# 2_FPGA.net
KiCad netlist of a schematic drawn in Altium Designer
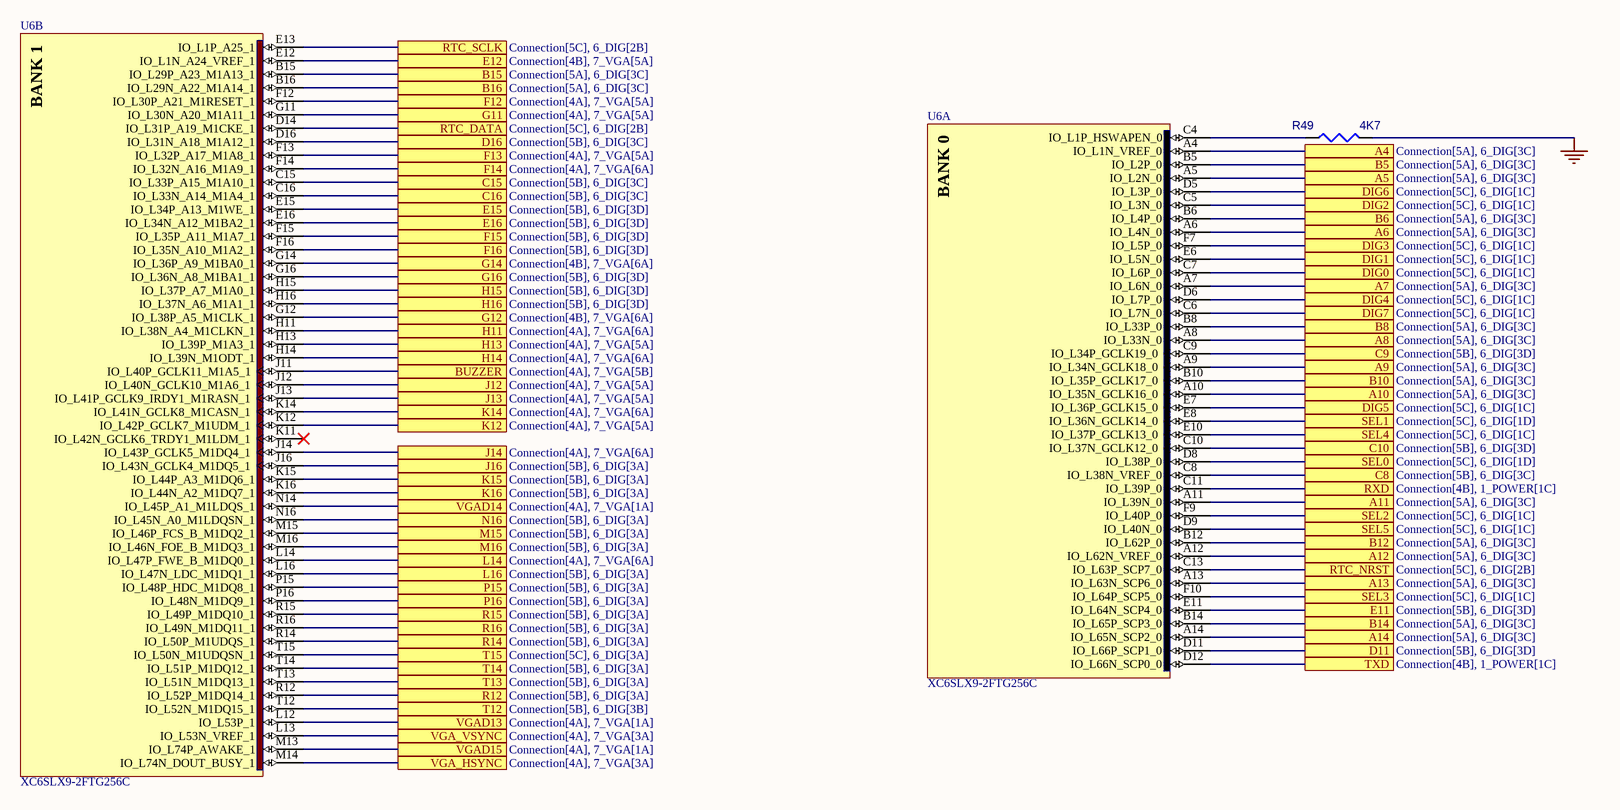
[diagram p0: 2_FPGA.SchDoc]

(export (version "E")
  (design (tool "Eeschema 10.0.6"))
  (components
    (comp (ref "R49") (value "4K7") (footprint "0603") (libsource (lib "*") (part "R")))
    (comp (ref "U6")
      (value "XC6SLX9-2FTG256C")
      (footprint "FTG256")
      (libsource (lib "Xilinx Spartan-6") (part "XC6SLX9-2FTG256C"))
    )
  )
  (nets
    (net (code "1") (name "/A4") (class "Default")
      (node (ref "U6") (pin "A4") (pinfunction "IO_L1N_VREF_0_A4") (pintype "bidirectional"))
    )
    (net (code "2") (name "/A5") (class "Default")
      (node (ref "U6") (pin "A5") (pinfunction "IO_L2N_0_A5") (pintype "bidirectional"))
    )
    (net (code "3") (name "/A6") (class "Default")
      (node (ref "U6") (pin "A6") (pinfunction "IO_L4N_0_A6") (pintype "bidirectional"))
    )
    (net (code "4") (name "/A7") (class "Default")
      (node (ref "U6") (pin "A7") (pinfunction "IO_L6N_0_A7") (pintype "bidirectional"))
    )
    (net (code "5") (name "/A8") (class "Default")
      (node (ref "U6") (pin "A8") (pinfunction "IO_L33N_0_A8") (pintype "bidirectional"))
    )
    (net (code "6") (name "/A9") (class "Default")
      (node (ref "U6") (pin "A9") (pinfunction "IO_L34N_GCLK18_0_A9") (pintype "bidirectional"))
    )
    (net (code "7") (name "/A10") (class "Default")
      (node (ref "U6") (pin "A10") (pinfunction "IO_L35N_GCLK16_0_A10") (pintype "bidirectional"))
    )
    (net (code "8") (name "/A11") (class "Default")
      (node (ref "U6") (pin "A11") (pinfunction "IO_L39N_0_A11") (pintype "bidirectional"))
    )
    (net (code "9") (name "/A12") (class "Default")
      (node (ref "U6") (pin "A12") (pinfunction "IO_L62N_VREF_0_A12") (pintype "bidirectional"))
    )
    (net (code "10") (name "/A13") (class "Default")
      (node (ref "U6") (pin "A13") (pinfunction "IO_L63N_SCP6_0_A13") (pintype "bidirectional"))
    )
    (net (code "11") (name "/A14") (class "Default")
      (node (ref "U6") (pin "A14") (pinfunction "IO_L65N_SCP2_0_A14") (pintype "bidirectional"))
    )
    (net (code "12") (name "/B5") (class "Default")
      (node (ref "U6") (pin "B5") (pinfunction "IO_L2P_0_B5") (pintype "bidirectional"))
    )
    (net (code "13") (name "/B6") (class "Default")
      (node (ref "U6") (pin "B6") (pinfunction "IO_L4P_0_B6") (pintype "bidirectional"))
    )
    (net (code "14") (name "/B8") (class "Default")
      (node (ref "U6") (pin "B8") (pinfunction "IO_L33P_0_B8") (pintype "bidirectional"))
    )
    (net (code "15") (name "/B10") (class "Default")
      (node (ref "U6") (pin "B10") (pinfunction "IO_L35P_GCLK17_0_B10") (pintype "bidirectional"))
    )
    (net (code "16") (name "/B12") (class "Default")
      (node (ref "U6") (pin "B12") (pinfunction "IO_L62P_0_B12") (pintype "bidirectional"))
    )
    (net (code "17") (name "/B14") (class "Default")
      (node (ref "U6") (pin "B14") (pinfunction "IO_L65P_SCP3_0_B14") (pintype "bidirectional"))
    )
    (net (code "18") (name "/B15") (class "Default")
      (node (ref "U6") (pin "B15") (pinfunction "IO_L29P_A23_M1A13_1_B15") (pintype "bidirectional"))
    )
    (net (code "19") (name "/B16") (class "Default")
      (node (ref "U6") (pin "B16") (pinfunction "IO_L29N_A22_M1A14_1_B16") (pintype "bidirectional"))
    )
    (net (code "20") (name "/BUZZER") (class "Default")
      (node (ref "U6") (pin "J11") (pinfunction "IO_L40P_GCLK11_M1A5_1_J11") (pintype "bidirectional"))
    )
    (net (code "21") (name "/C8") (class "Default")
      (node (ref "U6") (pin "C8") (pinfunction "IO_L38N_VREF_0_C8") (pintype "bidirectional"))
    )
    (net (code "22") (name "/C9") (class "Default")
      (node (ref "U6") (pin "C9") (pinfunction "IO_L34P_GCLK19_0_C9") (pintype "bidirectional"))
    )
    (net (code "23") (name "/C10") (class "Default")
      (node (ref "U6") (pin "C10") (pinfunction "IO_L37N_GCLK12_0_C10") (pintype "bidirectional"))
    )
    (net (code "24") (name "/C15") (class "Default")
      (node (ref "U6") (pin "C15") (pinfunction "IO_L33P_A15_M1A10_1_C15") (pintype "bidirectional"))
    )
    (net (code "25") (name "/C16") (class "Default")
      (node (ref "U6") (pin "C16") (pinfunction "IO_L33N_A14_M1A4_1_C16") (pintype "bidirectional"))
    )
    (net (code "26") (name "/D11") (class "Default")
      (node (ref "U6") (pin "D11") (pinfunction "IO_L66P_SCP1_0_D11") (pintype "bidirectional"))
    )
    (net (code "27") (name "/D16") (class "Default")
      (node (ref "U6") (pin "D16") (pinfunction "IO_L31N_A18_M1A12_1_D16") (pintype "bidirectional"))
    )
    (net (code "28") (name "/DIG0") (class "Default")
      (node (ref "U6") (pin "C7") (pinfunction "IO_L6P_0_C7") (pintype "bidirectional"))
    )
    (net (code "29") (name "/DIG1") (class "Default")
      (node (ref "U6") (pin "E6") (pinfunction "IO_L5N_0_E6") (pintype "bidirectional"))
    )
    (net (code "30") (name "/DIG2") (class "Default")
      (node (ref "U6") (pin "C5") (pinfunction "IO_L3N_0_C5") (pintype "bidirectional"))
    )
    (net (code "31") (name "/DIG3") (class "Default")
      (node (ref "U6") (pin "F7") (pinfunction "IO_L5P_0_F7") (pintype "bidirectional"))
    )
    (net (code "32") (name "/DIG4") (class "Default")
      (node (ref "U6") (pin "D6") (pinfunction "IO_L7P_0_D6") (pintype "bidirectional"))
    )
    (net (code "33") (name "/DIG5") (class "Default")
      (node (ref "U6") (pin "E7") (pinfunction "IO_L36P_GCLK15_0_E7") (pintype "bidirectional"))
    )
    (net (code "34") (name "/DIG6") (class "Default")
      (node (ref "U6") (pin "D5") (pinfunction "IO_L3P_0_D5") (pintype "bidirectional"))
    )
    (net (code "35") (name "/DIG7") (class "Default")
      (node (ref "U6") (pin "C6") (pinfunction "IO_L7N_0_C6") (pintype "bidirectional"))
    )
    (net (code "36") (name "/E11") (class "Default")
      (node (ref "U6") (pin "E11") (pinfunction "IO_L64N_SCP4_0_E11") (pintype "bidirectional"))
    )
    (net (code "37") (name "/E12") (class "Default")
      (node (ref "U6") (pin "E12") (pinfunction "IO_L1N_A24_VREF_1_E12") (pintype "bidirectional"))
    )
    (net (code "38") (name "/E15") (class "Default")
      (node (ref "U6") (pin "E15") (pinfunction "IO_L34P_A13_M1WE_1_E15") (pintype "bidirectional"))
    )
    (net (code "39") (name "/E16") (class "Default")
      (node (ref "U6") (pin "E16") (pinfunction "IO_L34N_A12_M1BA2_1_E16") (pintype "bidirectional"))
    )
    (net (code "40") (name "/F12") (class "Default")
      (node (ref "U6") (pin "F12") (pinfunction "IO_L30P_A21_M1RESET_1_F12") (pintype "bidirectional"))
    )
    (net (code "41") (name "/F13") (class "Default")
      (node (ref "U6") (pin "F13") (pinfunction "IO_L32P_A17_M1A8_1_F13") (pintype "bidirectional"))
    )
    (net (code "42") (name "/F14") (class "Default")
      (node (ref "U6") (pin "F14") (pinfunction "IO_L32N_A16_M1A9_1_F14") (pintype "bidirectional"))
    )
    (net (code "43") (name "/F15") (class "Default")
      (node (ref "U6") (pin "F15") (pinfunction "IO_L35P_A11_M1A7_1_F15") (pintype "bidirectional"))
    )
    (net (code "44") (name "/F16") (class "Default")
      (node (ref "U6") (pin "F16") (pinfunction "IO_L35N_A10_M1A2_1_F16") (pintype "bidirectional"))
    )
    (net (code "45") (name "/G11") (class "Default")
      (node (ref "U6") (pin "G11") (pinfunction "IO_L30N_A20_M1A11_1_G11") (pintype "bidirectional"))
    )
    (net (code "46") (name "/G12") (class "Default")
      (node (ref "U6") (pin "G12") (pinfunction "IO_L38P_A5_M1CLK_1_G12") (pintype "bidirectional"))
    )
    (net (code "47") (name "/G14") (class "Default")
      (node (ref "U6") (pin "G14") (pinfunction "IO_L36P_A9_M1BA0_1_G14") (pintype "bidirectional"))
    )
    (net (code "48") (name "/G16") (class "Default")
      (node (ref "U6") (pin "G16") (pinfunction "IO_L36N_A8_M1BA1_1_G16") (pintype "bidirectional"))
    )
    (net (code "49") (name "/H11") (class "Default")
      (node (ref "U6") (pin "H11") (pinfunction "IO_L38N_A4_M1CLKN_1_H11") (pintype "bidirectional"))
    )
    (net (code "50") (name "/H13") (class "Default")
      (node (ref "U6") (pin "H13") (pinfunction "IO_L39P_M1A3_1_H13") (pintype "bidirectional"))
    )
    (net (code "51") (name "/H14") (class "Default")
      (node (ref "U6") (pin "H14") (pinfunction "IO_L39N_M1ODT_1_H14") (pintype "bidirectional"))
    )
    (net (code "52") (name "/H15") (class "Default")
      (node (ref "U6") (pin "H15") (pinfunction "IO_L37P_A7_M1A0_1_H15") (pintype "bidirectional"))
    )
    (net (code "53") (name "/H16") (class "Default")
      (node (ref "U6") (pin "H16") (pinfunction "IO_L37N_A6_M1A1_1_H16") (pintype "bidirectional"))
    )
    (net (code "54") (name "/J12") (class "Default")
      (node (ref "U6") (pin "J12") (pinfunction "IO_L40N_GCLK10_M1A6_1_J12") (pintype "bidirectional"))
    )
    (net (code "55") (name "/J13") (class "Default")
      (node (ref "U6") (pin "J13") (pinfunction "IO_L41P_GCLK9_IRDY1_M1RASN_1_J13") (pintype "bidirectional"))
    )
    (net (code "56") (name "/J14") (class "Default")
      (node (ref "U6") (pin "J14") (pinfunction "IO_L43P_GCLK5_M1DQ4_1_J14") (pintype "bidirectional"))
    )
    (net (code "57") (name "/J16") (class "Default")
      (node (ref "U6") (pin "J16") (pinfunction "IO_L43N_GCLK4_M1DQ5_1_J16") (pintype "bidirectional"))
    )
    (net (code "58") (name "/K12") (class "Default")
      (node (ref "U6") (pin "K12") (pinfunction "IO_L42P_GCLK7_M1UDM_1_K12") (pintype "bidirectional"))
    )
    (net (code "59") (name "/K14") (class "Default")
      (node (ref "U6") (pin "K14") (pinfunction "IO_L41N_GCLK8_M1CASN_1_K14") (pintype "bidirectional"))
    )
    (net (code "60") (name "/K15") (class "Default")
      (node (ref "U6") (pin "K15") (pinfunction "IO_L44P_A3_M1DQ6_1_K15") (pintype "bidirectional"))
    )
    (net (code "61") (name "/K16") (class "Default")
      (node (ref "U6") (pin "K16") (pinfunction "IO_L44N_A2_M1DQ7_1_K16") (pintype "bidirectional"))
    )
    (net (code "62") (name "/L14") (class "Default")
      (node (ref "U6") (pin "L14") (pinfunction "IO_L47P_FWE_B_M1DQ0_1_L14") (pintype "bidirectional"))
    )
    (net (code "63") (name "/L16") (class "Default")
      (node (ref "U6") (pin "L16") (pinfunction "IO_L47N_LDC_M1DQ1_1_L16") (pintype "bidirectional"))
    )
    (net (code "64") (name "/M15") (class "Default")
      (node (ref "U6") (pin "M15") (pinfunction "IO_L46P_FCS_B_M1DQ2_1_M15") (pintype "bidirectional"))
    )
    (net (code "65") (name "/M16") (class "Default")
      (node (ref "U6") (pin "M16") (pinfunction "IO_L46N_FOE_B_M1DQ3_1_M16") (pintype "bidirectional"))
    )
    (net (code "66") (name "/N16") (class "Default")
      (node (ref "U6") (pin "N16") (pinfunction "IO_L45N_A0_M1LDQSN_1_N16") (pintype "bidirectional"))
    )
    (net (code "67") (name "/P15") (class "Default")
      (node (ref "U6") (pin "P15") (pinfunction "IO_L48P_HDC_M1DQ8_1_P15") (pintype "bidirectional"))
    )
    (net (code "68") (name "/P16") (class "Default")
      (node (ref "U6") (pin "P16") (pinfunction "IO_L48N_M1DQ9_1_P16") (pintype "bidirectional"))
    )
    (net (code "69") (name "/R12") (class "Default")
      (node (ref "U6") (pin "R12") (pinfunction "IO_L52P_M1DQ14_1_R12") (pintype "bidirectional"))
    )
    (net (code "70") (name "/R14") (class "Default")
      (node (ref "U6") (pin "R14") (pinfunction "IO_L50P_M1UDQS_1_R14") (pintype "bidirectional"))
    )
    (net (code "71") (name "/R15") (class "Default")
      (node (ref "U6") (pin "R15") (pinfunction "IO_L49P_M1DQ10_1_R15") (pintype "bidirectional"))
    )
    (net (code "72") (name "/R16") (class "Default")
      (node (ref "U6") (pin "R16") (pinfunction "IO_L49N_M1DQ11_1_R16") (pintype "bidirectional"))
    )
    (net (code "73") (name "/RTC_DATA") (class "Default")
      (node (ref "U6") (pin "D14") (pinfunction "IO_L31P_A19_M1CKE_1_D14") (pintype "bidirectional"))
    )
    (net (code "74") (name "/RTC_NRST") (class "Default")
      (node (ref "U6") (pin "C13") (pinfunction "IO_L63P_SCP7_0_C13") (pintype "bidirectional"))
    )
    (net (code "75") (name "/RTC_SCLK") (class "Default")
      (node (ref "U6") (pin "E13") (pinfunction "IO_L1P_A25_1_E13") (pintype "bidirectional"))
    )
    (net (code "76") (name "/RXD") (class "Default")
      (node (ref "U6") (pin "C11") (pinfunction "IO_L39P_0_C11") (pintype "bidirectional"))
    )
    (net (code "77") (name "/SEL0") (class "Default")
      (node (ref "U6") (pin "D8") (pinfunction "IO_L38P_0_D8") (pintype "bidirectional"))
    )
    (net (code "78") (name "/SEL1") (class "Default")
      (node (ref "U6") (pin "E8") (pinfunction "IO_L36N_GCLK14_0_E8") (pintype "bidirectional"))
    )
    (net (code "79") (name "/SEL2") (class "Default")
      (node (ref "U6") (pin "F9") (pinfunction "IO_L40P_0_F9") (pintype "bidirectional"))
    )
    (net (code "80") (name "/SEL3") (class "Default")
      (node (ref "U6") (pin "F10") (pinfunction "IO_L64P_SCP5_0_F10") (pintype "bidirectional"))
    )
    (net (code "81") (name "/SEL4") (class "Default")
      (node (ref "U6") (pin "E10") (pinfunction "IO_L37P_GCLK13_0_E10") (pintype "bidirectional"))
    )
    (net (code "82") (name "/SEL5") (class "Default")
      (node (ref "U6") (pin "D9") (pinfunction "IO_L40N_0_D9") (pintype "bidirectional"))
    )
    (net (code "83") (name "/T12") (class "Default")
      (node (ref "U6") (pin "T12") (pinfunction "IO_L52N_M1DQ15_1_T12") (pintype "bidirectional"))
    )
    (net (code "84") (name "/T13") (class "Default")
      (node (ref "U6") (pin "T13") (pinfunction "IO_L51N_M1DQ13_1_T13") (pintype "bidirectional"))
    )
    (net (code "85") (name "/T14") (class "Default")
      (node (ref "U6") (pin "T14") (pinfunction "IO_L51P_M1DQ12_1_T14") (pintype "bidirectional"))
    )
    (net (code "86") (name "/T15") (class "Default")
      (node (ref "U6") (pin "T15") (pinfunction "IO_L50N_M1UDQSN_1_T15") (pintype "bidirectional"))
    )
    (net (code "87") (name "/TXD") (class "Default")
      (node (ref "U6") (pin "D12") (pinfunction "IO_L66N_SCP0_0_D12") (pintype "bidirectional"))
    )
    (net (code "88") (name "/VGAD13") (class "Default")
      (node (ref "U6") (pin "L12") (pinfunction "IO_L53P_1_L12") (pintype "bidirectional"))
    )
    (net (code "89") (name "/VGAD14") (class "Default")
      (node (ref "U6") (pin "N14") (pinfunction "IO_L45P_A1_M1LDQS_1_N14") (pintype "bidirectional"))
    )
    (net (code "90") (name "/VGAD15") (class "Default")
      (node (ref "U6") (pin "M13") (pinfunction "IO_L74P_AWAKE_1_M13") (pintype "bidirectional"))
    )
    (net (code "91") (name "/VGA_HSYNC") (class "Default")
      (node (ref "U6") (pin "M14") (pinfunction "IO_L74N_DOUT_BUSY_1_M14") (pintype "bidirectional"))
    )
    (net (code "92") (name "/VGA_VSYNC") (class "Default")
      (node (ref "U6") (pin "L13") (pinfunction "IO_L53N_VREF_1_L13") (pintype "bidirectional"))
    )
    (net (code "93") (name "GND") (class "Default")
      (node (ref "R49") (pin "2") (pinfunction "2_2") (pintype "passive"))
    )
    (net (code "94") (name "Net-(U6A-IO_L1P_HSWAPEN_0)") (class "Default")
      (node (ref "R49") (pin "1") (pinfunction "1_1") (pintype "passive"))
      (node (ref "U6") (pin "C4") (pinfunction "IO_L1P_HSWAPEN_0_C4") (pintype "bidirectional"))
    )
    (net (code "95") (name "unconnected-(U6B-IO_L42N_GCLK6_TRDY1_M1LDM_1-PadK11)") (class "Default")
      (node (ref "U6") (pin "K11") (pinfunction "IO_L42N_GCLK6_TRDY1_M1LDM_1_K11") (pintype "bidirectional+no_connect"))
    )
  )
)
